# POWERSYSTEM.net
KiCad netlist of a schematic drawn in Altium Designer
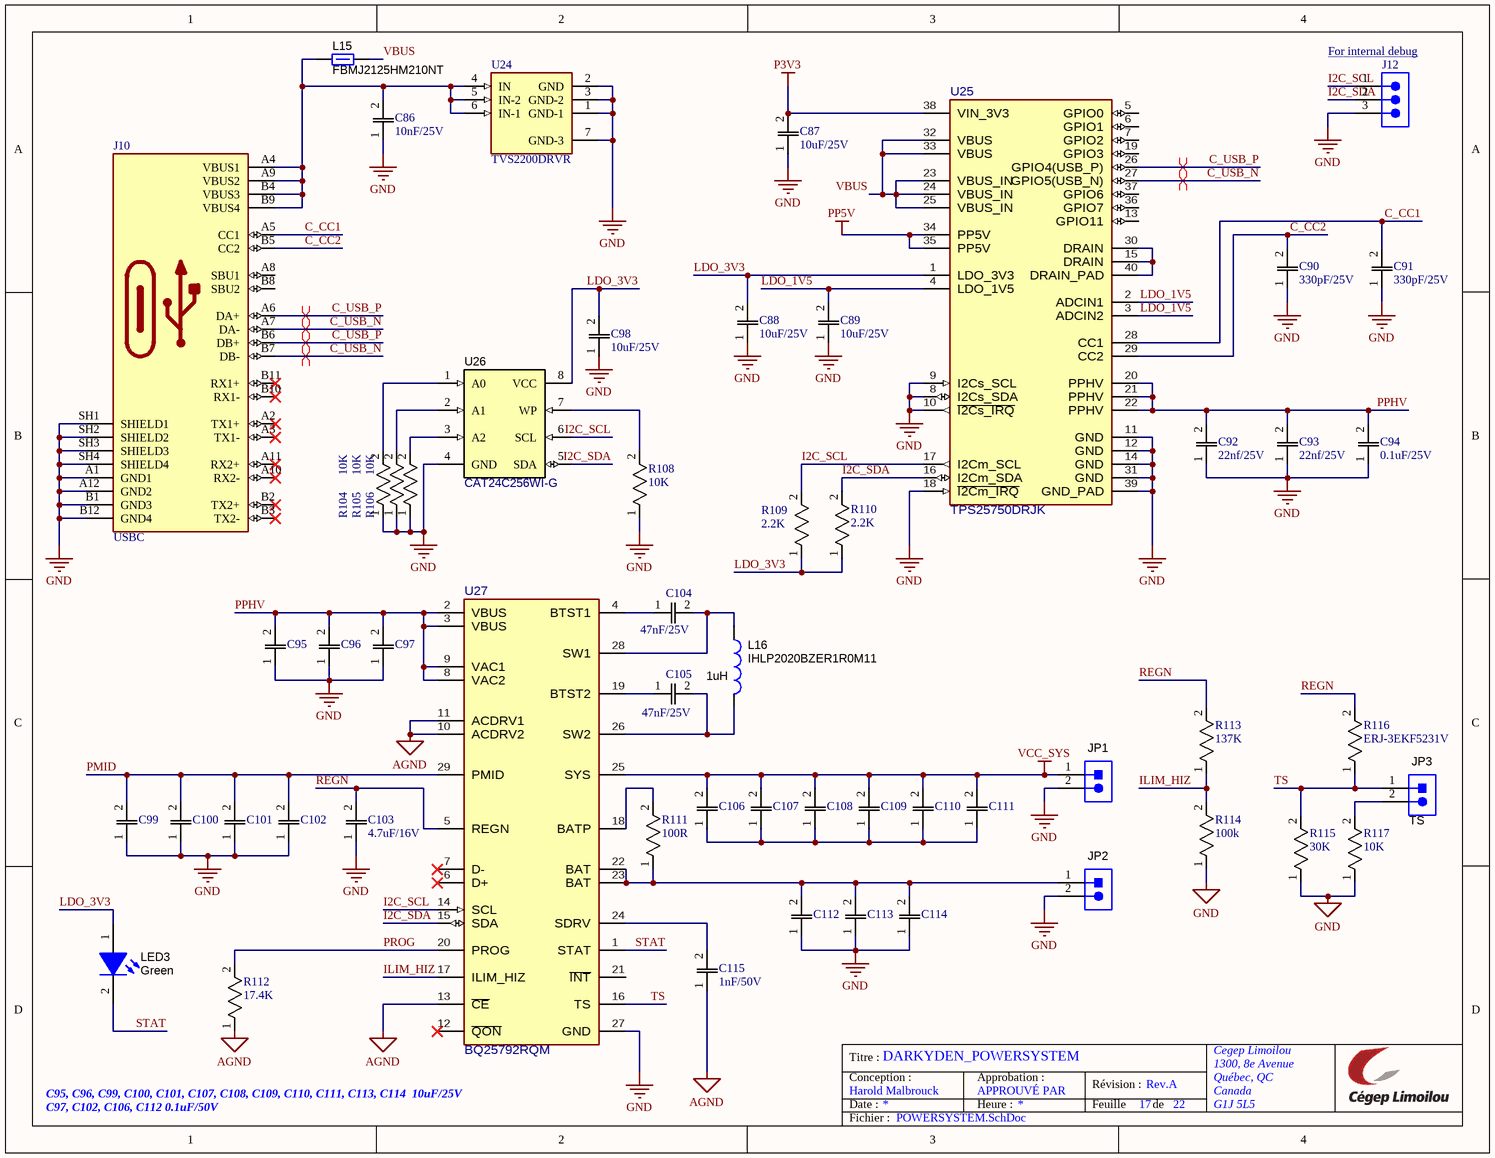
[diagram p0: POWERSYSTEM.SchDoc]

(export (version "E")
  (design (tool "Eeschema 10.0.6"))
  (components
    (comp (ref "C86")
      (value "10nF/25V")
      (footprint "SamacSys:C0805")
      (description "SMD Comm X7R")
      (fields (field (name "MANUFACTURER_PART_NUMBER") "C0805C103K3RACTU"))
      (libsource (lib "SamacSys") (part "C0805C103K3RACTU"))
    )
    (comp (ref "C87")
      (value "10uF/25V")
      (footprint "CAPC220145_88N_KEM")
      (description "10uF / 25 VDC, +85degC, X5R Dielec, +/-10% ¦ KEMET C0805C106K3PACTU 0805")
      (fields
        (field (name "MANUFACTURER") "KEMET")
        (field (name "MANUFACTURER PART NUMBER") "C0805C106K3PACTU")
      )
      (libsource (lib "C0805C106K3PACTU") (part "C0805C106K3PACTU"))
    )
    (comp (ref "C88")
      (value "10uF/25V")
      (footprint "CAPC220145_88N_KEM")
      (description "10uF / 25 VDC, +85degC, X5R Dielec, +/-10% ¦ KEMET C0805C106K3PACTU 0805")
      (fields
        (field (name "MANUFACTURER") "KEMET")
        (field (name "MANUFACTURER PART NUMBER") "C0805C106K3PACTU")
      )
      (libsource (lib "C0805C106K3PACTU") (part "C0805C106K3PACTU"))
    )
    (comp (ref "C89")
      (value "10uF/25V")
      (footprint "CAPC220145_88N_KEM")
      (description "10uF / 25 VDC, +85degC, X5R Dielec, +/-10% ¦ KEMET C0805C106K3PACTU 0805")
      (fields
        (field (name "MANUFACTURER") "KEMET")
        (field (name "MANUFACTURER PART NUMBER") "C0805C106K3PACTU")
      )
      (libsource (lib "C0805C106K3PACTU") (part "C0805C106K3PACTU"))
    )
    (comp (ref "C90")
      (value "330pF/25V")
      (footprint "SamacSys:C0805")
      (description "330pF/25V  C0G 0805 10%")
      (fields
        (field (name "MANUFACTURER_PART_NUMBER") "C0805C331K3GACTU")
        (field (name "MOUSER PART NUMBER") "80-C0805C331K3G")
      )
      (libsource (lib "SamacSys") (part "C0805C331K3GACTU"))
    )
    (comp (ref "C91")
      (value "330pF/25V")
      (footprint "SamacSys:C0805")
      (description "330pF/25V  C0G 0805 10%")
      (fields
        (field (name "MANUFACTURER_PART_NUMBER") "C0805C331K3GACTU")
        (field (name "MOUSER PART NUMBER") "80-C0805C331K3G")
      )
      (libsource (lib "SamacSys") (part "C0805C331K3GACTU"))
    )
    (comp (ref "C92")
      (value "22nf/25V")
      (footprint "SamacSys:C0805")
      (description "SMD Multilayer Ceramic Capacitor, 0.022 ï¿½F, 25 V, 0805 [2012 Metric], ï¿½ 5%, C0G / NP0")
      (fields
        (field (name "MANUFACTURER_PART_NUMBER") "C0805C223J3GACTU")
        (field (name "MANUFACTURER") "KEMET")
      )
      (libsource (lib "SamacSys") (part "C0805C223J3GACTU"))
    )
    (comp (ref "C93")
      (value "22nf/25V")
      (footprint "SamacSys:C0805")
      (description "SMD Multilayer Ceramic Capacitor, 0.022 ï¿½F, 25 V, 0805 [2012 Metric], ï¿½ 5%, C0G / NP0")
      (fields
        (field (name "MANUFACTURER_PART_NUMBER") "C0805C223J3GACTU")
        (field (name "MANUFACTURER") "KEMET")
      )
      (libsource (lib "SamacSys") (part "C0805C223J3GACTU"))
    )
    (comp (ref "C94")
      (value "0.1uF/25V")
      (footprint "CAPC220145_88N_KEM")
      (description "0.1uF 25V X7R 10% SMD 0805 125C Plastic T/R")
      (fields
        (field (name "MANUFACTURER") "KEMET")
        (field (name "MANUFACTURER PART NUMBER") "C0805C104K3RACTU")
      )
      (libsource (lib "C0805C104K3RACTU") (part "C0805C104K3RACTU"))
    )
    (comp (ref "C95")
      (value "10uF/25V")
      (footprint "CAPC220145_88N_KEM")
      (description "10uF / 25 VDC, +85degC, X5R Dielec, +/-10% ¦ KEMET C0805C106K3PACTU 0805")
      (fields
        (field (name "MANUFACTURER") "KEMET")
        (field (name "MANUFACTURER PART NUMBER") "C0805C106K3PACTU")
      )
      (libsource (lib "C0805C106K3PACTU") (part "C0805C106K3PACTU"))
    )
    (comp (ref "C96")
      (value "10uF/25V")
      (footprint "CAPC220145_88N_KEM")
      (description "10uF / 25 VDC, +85degC, X5R Dielec, +/-10% ¦ KEMET C0805C106K3PACTU 0805")
      (fields
        (field (name "MANUFACTURER") "KEMET")
        (field (name "MANUFACTURER PART NUMBER") "C0805C106K3PACTU")
      )
      (libsource (lib "C0805C106K3PACTU") (part "C0805C106K3PACTU"))
    )
    (comp (ref "C97")
      (value "0.1uF/50V")
      (footprint "SamacSys:C0805")
      (description "SMD Comm X7R")
      (fields (field (name "MANUFACTURER_PART_NUMBER") "C0805C104K5RACTU"))
      (libsource (lib "SamacSys") (part "C0805C104K5RACTU"))
    )
    (comp (ref "C98")
      (value "10uF/25V")
      (footprint "CAPC220145_88N_KEM")
      (description "10uF / 25 VDC, +85degC, X5R Dielec, +/-10% ¦ KEMET C0805C106K3PACTU 0805")
      (fields
        (field (name "MANUFACTURER") "KEMET")
        (field (name "MANUFACTURER PART NUMBER") "C0805C106K3PACTU")
      )
      (libsource (lib "C0805C106K3PACTU") (part "C0805C106K3PACTU"))
    )
    (comp (ref "C99")
      (value "10uF/25V")
      (footprint "CAPC220145_88N_KEM")
      (description "10uF / 25 VDC, +85degC, X5R Dielec, +/-10% ¦ KEMET C0805C106K3PACTU 0805")
      (fields
        (field (name "MANUFACTURER") "KEMET")
        (field (name "MANUFACTURER PART NUMBER") "C0805C106K3PACTU")
      )
      (libsource (lib "C0805C106K3PACTU") (part "C0805C106K3PACTU"))
    )
    (comp (ref "C100")
      (value "10uF/25V")
      (footprint "CAPC220145_88N_KEM")
      (description "10uF / 25 VDC, +85degC, X5R Dielec, +/-10% ¦ KEMET C0805C106K3PACTU 0805")
      (fields
        (field (name "MANUFACTURER") "KEMET")
        (field (name "MANUFACTURER PART NUMBER") "C0805C106K3PACTU")
      )
      (libsource (lib "C0805C106K3PACTU") (part "C0805C106K3PACTU"))
    )
    (comp (ref "C101")
      (value "10uF/25V")
      (footprint "CAPC220145_88N_KEM")
      (description "10uF / 25 VDC, +85degC, X5R Dielec, +/-10% ¦ KEMET C0805C106K3PACTU 0805")
      (fields
        (field (name "MANUFACTURER") "KEMET")
        (field (name "MANUFACTURER PART NUMBER") "C0805C106K3PACTU")
      )
      (libsource (lib "C0805C106K3PACTU") (part "C0805C106K3PACTU"))
    )
    (comp (ref "C102")
      (value "0.1uF/50V")
      (footprint "SamacSys:C0805")
      (description "SMD Comm X7R")
      (fields (field (name "MANUFACTURER_PART_NUMBER") "C0805C104K5RACTU"))
      (libsource (lib "SamacSys") (part "C0805C104K5RACTU"))
    )
    (comp (ref "C103")
      (value "4.7uF/16V")
      (footprint "SamacSys:C0805")
      (description "4.7 uF, 16 V, ± 10%, X7R, 0805 [2012 Metric]")
      (fields
        (field (name "MANUFACTURER_PART_NUMBER") "C0805C475K4RACTU")
        (field (name "MOUSER PART NUMBER") "80-C0805C475K4R")
      )
      (libsource (lib "SamacSys") (part "C0805C475K4RACTU"))
    )
    (comp (ref "C104")
      (value "47nF/25V")
      (footprint "SamacSys:C0805")
      (description "47nF /25 V, +125degC, C0G Dielectric, +/-5% ¦ KEMET C0805C473J3GACTU")
      (fields
        (field (name "MANUFACTURER_PART_NUMBER") "C0805C473J3GACTU")
        (field (name "MOUSER PART NUMBER") "80-C0805C473J3G")
      )
      (libsource (lib "SamacSys") (part "C0805C473J3GACTU"))
    )
    (comp (ref "C105")
      (value "47nF/25V")
      (footprint "SamacSys:C0805")
      (description "47nF /25 V, +125degC, C0G Dielectric, +/-5% ¦ KEMET C0805C473J3GACTU")
      (fields
        (field (name "MANUFACTURER_PART_NUMBER") "C0805C473J3GACTU")
        (field (name "MOUSER PART NUMBER") "80-C0805C473J3G")
      )
      (libsource (lib "SamacSys") (part "C0805C473J3GACTU"))
    )
    (comp (ref "C106")
      (value "0.1uF/50V")
      (footprint "SamacSys:C0805")
      (description "SMD Comm X7R")
      (fields (field (name "MANUFACTURER_PART_NUMBER") "C0805C104K5RACTU"))
      (libsource (lib "SamacSys") (part "C0805C104K5RACTU"))
    )
    (comp (ref "C107")
      (value "10uF/25V")
      (footprint "CAPC220145_88N_KEM")
      (description "10uF / 25 VDC, +85degC, X5R Dielec, +/-10% ¦ KEMET C0805C106K3PACTU 0805")
      (fields
        (field (name "MANUFACTURER") "KEMET")
        (field (name "MANUFACTURER PART NUMBER") "C0805C106K3PACTU")
      )
      (libsource (lib "C0805C106K3PACTU") (part "C0805C106K3PACTU"))
    )
    (comp (ref "C108")
      (value "10uF/25V")
      (footprint "CAPC220145_88N_KEM")
      (description "10uF / 25 VDC, +85degC, X5R Dielec, +/-10% ¦ KEMET C0805C106K3PACTU 0805")
      (fields
        (field (name "MANUFACTURER") "KEMET")
        (field (name "MANUFACTURER PART NUMBER") "C0805C106K3PACTU")
      )
      (libsource (lib "C0805C106K3PACTU") (part "C0805C106K3PACTU"))
    )
    (comp (ref "C109")
      (value "10uF/25V")
      (footprint "CAPC220145_88N_KEM")
      (description "10uF / 25 VDC, +85degC, X5R Dielec, +/-10% ¦ KEMET C0805C106K3PACTU 0805")
      (fields
        (field (name "MANUFACTURER") "KEMET")
        (field (name "MANUFACTURER PART NUMBER") "C0805C106K3PACTU")
      )
      (libsource (lib "C0805C106K3PACTU") (part "C0805C106K3PACTU"))
    )
    (comp (ref "C110")
      (value "10uF/25V")
      (footprint "CAPC220145_88N_KEM")
      (description "10uF / 25 VDC, +85degC, X5R Dielec, +/-10% ¦ KEMET C0805C106K3PACTU 0805")
      (fields
        (field (name "MANUFACTURER") "KEMET")
        (field (name "MANUFACTURER PART NUMBER") "C0805C106K3PACTU")
      )
      (libsource (lib "C0805C106K3PACTU") (part "C0805C106K3PACTU"))
    )
    (comp (ref "C111")
      (value "10uF/25V")
      (footprint "CAPC220145_88N_KEM")
      (description "10uF / 25 VDC, +85degC, X5R Dielec, +/-10% ¦ KEMET C0805C106K3PACTU 0805")
      (fields
        (field (name "MANUFACTURER") "KEMET")
        (field (name "MANUFACTURER PART NUMBER") "C0805C106K3PACTU")
      )
      (libsource (lib "C0805C106K3PACTU") (part "C0805C106K3PACTU"))
    )
    (comp (ref "C112")
      (value "0.1uF/50V")
      (footprint "SamacSys:C0805")
      (description "SMD Comm X7R")
      (fields (field (name "MANUFACTURER_PART_NUMBER") "C0805C104K5RACTU"))
      (libsource (lib "SamacSys") (part "C0805C104K5RACTU"))
    )
    (comp (ref "C113")
      (value "10uF/25V")
      (footprint "CAPC220145_88N_KEM")
      (description "10uF / 25 VDC, +85degC, X5R Dielec, +/-10% ¦ KEMET C0805C106K3PACTU 0805")
      (fields
        (field (name "MANUFACTURER") "KEMET")
        (field (name "MANUFACTURER PART NUMBER") "C0805C106K3PACTU")
      )
      (libsource (lib "C0805C106K3PACTU") (part "C0805C106K3PACTU"))
    )
    (comp (ref "C114")
      (value "10uF/25V")
      (footprint "CAPC220145_88N_KEM")
      (description "10uF / 25 VDC, +85degC, X5R Dielec, +/-10% ¦ KEMET C0805C106K3PACTU 0805")
      (fields
        (field (name "MANUFACTURER") "KEMET")
        (field (name "MANUFACTURER PART NUMBER") "C0805C106K3PACTU")
      )
      (libsource (lib "C0805C106K3PACTU") (part "C0805C106K3PACTU"))
    )
    (comp (ref "C115")
      (value "1nF/50V")
      (footprint "SamacSys:CAPC2012X88N")
      (description "Multilayer Ceramic Capacitor 1000 Pf 50 V ½ 10% X7R 0805 [2012 Metric]")
      (fields
        (field (name "MANUFACTURER_PART_NUMBER") "C0805C102K5RAC-TU")
        (field (name "MANUFACTURER") "KEMET")
      )
      (libsource (lib "SamacSys") (part "C0805C102K5RACTU"))
    )
    (comp (ref "J10")
      (value "USBC")
      (footprint "MOLEX_2012670005")
      (fields (field (name "MF") "Molex") (field (name "MP") "2012670005"))
      (libsource (lib "USBC") (part "USBC"))
    )
    (comp (ref "J12")
      (value "61300311121")
      (footprint "61300311121")
      (description "WR-PHD Pin Header, THT, Vertical, pitch 2.54mm, 1 Row, 3P")
      (fields (field (name "MANUFACTURER") "Wurth Elektronik"))
      (libsource (lib "Header") (part "61300311121"))
    )
    (comp (ref "JP1")
      (value "Header_2x1")
      (footprint "CONN_PEC02SAAN")
      (description "Header, 100mil, 2x1, Tin, TH")
      (fields
        (field (name "PARTNUMBER") "PEC02SAAN")
        (field (name "MANUFACTURER") "Sullins Connector Solutions")
        (field (name "PUBLISHER") "Texas Instruments")
      )
      (libsource (lib "texas_instrument_power") (part "Header_2x1"))
    )
    (comp (ref "JP2")
      (value "Header_2x1")
      (footprint "CONN_PEC02SAAN")
      (description "Header, 100mil, 2x1, Tin, TH")
      (fields
        (field (name "PARTNUMBER") "PEC02SAAN")
        (field (name "MANUFACTURER") "Sullins Connector Solutions")
        (field (name "PUBLISHER") "Texas Instruments")
      )
      (libsource (lib "texas_instrument_power") (part "Header_2x1"))
    )
    (comp (ref "JP3")
      (value "TS")
      (footprint "CONN_PEC02SAAN")
      (description "Header, 100mil, 2x1, Tin, TH")
      (fields
        (field (name "PARTNUMBER") "PEC02SAAN")
        (field (name "MANUFACTURER") "Sullins Connector Solutions")
        (field (name "PUBLISHER") "Texas Instruments")
      )
      (libsource (lib "texas_instrument_power") (part "Header_2x1"))
    )
    (comp (ref "L15")
      (value "FBMJ2125HM210NT")
      (footprint "0805_HV")
      (description "Ferrite Bead, 21 ohm @ 100 MHz, 6 A, 0805")
      (fields (field (name "MANUFACTURER") "Taiyo Yuden") (field (name "PUBLISHER") "Texas Instruments"))
      (libsource (lib "Altium Vault - TI") (part "Ferrite_Bead"))
    )
    (comp (ref "L16")
      (value "IHLP2020BZER1R0M11")
      (footprint "IHLP-2020BZ")
      (description "Inductor, Shielded Drum Core, Powdered Iron, 1 uH, 7 A, 0.0181 ohm, SMD")
      (fields
        (field (name "MANUFACTURER") "Vishay-Dale")
        (field (name "VALUEDISPLAYED") "1uH")
        (field (name "PUBLISHER") "Texas Instruments")
      )
      (libsource (lib "texas_instrument_power") (part "IHLP2020BZER1R0M11"))
    )
    (comp (ref "LED3")
      (value "Green")
      (footprint "LED_LTST-C190")
      (description "LED, Green, SMD")
      (fields (field (name "MANUFACTURER") "Lite-On") (field (name "PARTNUMBER") "LTST-C190GKT"))
      (libsource (lib "texas_instrument_power") (part "LED_Gr_SMD"))
    )
    (comp (ref "R104")
      (value "10K")
      (footprint "SamacSys:ERJ3EKF1000V")
      (description "10K Ohm 5% Res Thick Film 0603  0.1W(1/10W) ±200ppm/C Pad SMD Automotive T/R")
      (fields
        (field (name "MANUFACTURER_PART_NUMBER") "ERJ-3GEYJ103V")
        (field (name "MOUSER PART NUMBER") "667-ERJ-3GEYJ103V")
      )
      (libsource (lib "SamacSys") (part "ERJ-3GEYJ103V"))
    )
    (comp (ref "R105")
      (value "10K")
      (footprint "SamacSys:ERJ3EKF1000V")
      (description "10K Ohm 5% Res Thick Film 0603  0.1W(1/10W) ±200ppm/C Pad SMD Automotive T/R")
      (fields
        (field (name "MANUFACTURER_PART_NUMBER") "ERJ-3GEYJ103V")
        (field (name "MOUSER PART NUMBER") "667-ERJ-3GEYJ103V")
      )
      (libsource (lib "SamacSys") (part "ERJ-3GEYJ103V"))
    )
    (comp (ref "R106")
      (value "10K")
      (footprint "SamacSys:ERJ3EKF1000V")
      (description "10K Ohm 5% Res Thick Film 0603  0.1W(1/10W) ±200ppm/C Pad SMD Automotive T/R")
      (fields
        (field (name "MANUFACTURER_PART_NUMBER") "ERJ-3GEYJ103V")
        (field (name "MOUSER PART NUMBER") "667-ERJ-3GEYJ103V")
      )
      (libsource (lib "SamacSys") (part "ERJ-3GEYJ103V"))
    )
    (comp (ref "R108")
      (value "10K")
      (footprint "SamacSys:ERJ3EKF1000V")
      (description "10K Ohm 5% Res Thick Film 0603  0.1W(1/10W) ±200ppm/C Pad SMD Automotive T/R")
      (fields
        (field (name "MANUFACTURER_PART_NUMBER") "ERJ-3GEYJ103V")
        (field (name "MOUSER PART NUMBER") "667-ERJ-3GEYJ103V")
      )
      (libsource (lib "SamacSys") (part "ERJ-3GEYJ103V"))
    )
    (comp (ref "R109")
      (value "2.2K")
      (footprint "SamacSys:ERJ3EKF1000V")
      (description "SMD Chip Resistor, 2.2 kOhm, ï¿½ 5%, 100 mW, 0603 [1608 Metric], Thick Film, General Purpose")
      (fields
        (field (name "MANUFACTURER_PART_NUMBER") "ERJ-3GEYJ222V")
        (field (name "MOUSER PART NUMBER") "667-ERJ-3GEYJ222V")
      )
      (libsource (lib "SamacSys") (part "ERJ-3GEYJ222V"))
    )
    (comp (ref "R110")
      (value "2.2K")
      (footprint "SamacSys:ERJ3EKF1000V")
      (description "SMD Chip Resistor, 2.2 kOhm, ï¿½ 5%, 100 mW, 0603 [1608 Metric], Thick Film, General Purpose")
      (fields
        (field (name "MANUFACTURER_PART_NUMBER") "ERJ-3GEYJ222V")
        (field (name "MOUSER PART NUMBER") "667-ERJ-3GEYJ222V")
      )
      (libsource (lib "SamacSys") (part "ERJ-3GEYJ222V"))
    )
    (comp (ref "R111")
      (value "100R")
      (footprint "SamacSys:RESC1608X55N")
      (description "100 Ohm 1% 1/10W 0603 ±100ppm/°C Molded SMD Punched Carrier T/R")
      (fields
        (field (name "MANUFACTURER_PART_NUMBER") "ERJ-3EKF1000V")
        (field (name "MOUSER PART NUMBER") "667-ERJ-3EKF1000V")
      )
      (libsource (lib "SamacSys") (part "ERJ-3EKF1000V"))
    )
    (comp (ref "R112")
      (value "17.4K")
      (footprint "SamacSys:RESC1608X55N")
      (description "Res Thick Film 0603 17.4K Ohm 1% 1/10W +/-100ppm/ßC Molded SMD Punched Carrier T/R")
      (fields
        (field (name "MANUFACTURER_PART_NUMBER") "ERJ-3EKF1742V")
        (field (name "MOUSER PART NUMBER") "667-ERJ-3EKF1742V")
      )
      (libsource (lib "SamacSys") (part "ERJ-3EKF1742V"))
    )
    (comp (ref "R113")
      (value "137K")
      (footprint "SamacSys:RESC1608X55N")
      (description "137K Ohm 1% 1/10W Res Thick Film 0603 ±100ppm/°C SMD Punched Carrier T/R")
      (fields
        (field (name "MANUFACTURER_PART_NUMBER") "ERJ-3EKF1373V")
        (field (name "MOUSER PART NUMBER") "667-ERJ-3EKF1373V")
      )
      (libsource (lib "SamacSys") (part "ERJ-3EKF1373V"))
    )
    (comp (ref "R114")
      (value "100k")
      (footprint "SamacSys:ERJ3EKF1000V")
      (description "100K Ohm 5%  Res Thick Film 0603 1/10W +/-200ppm/ßC Molded SMD Punched Carrier T/R")
      (fields
        (field (name "MANUFACTURER_PART_NUMBER") "ERJ-3GEYJ104V")
        (field (name "MOUSER PART NUMBER") "667-ERJ-3GEYJ104V")
      )
      (libsource (lib "SamacSys") (part "ERJ-3GEYJ104V"))
    )
    (comp (ref "R115")
      (value "30K")
      (footprint "SamacSys:ERJ3EKF1000V")
      (description "30K Ohm 5% 0.1W(1/10W) +/-200ppm/ßC Res Thick Film 0603  SMD Automotive T/R")
      (fields
        (field (name "MANUFACTURER_PART_NUMBER") "ERJ-3GEYJ303V")
        (field (name "MOUSER PART NUMBER") "667-ERJ-3GEYJ303V")
      )
      (libsource (lib "SamacSys") (part "ERJ-3GEYJ303V"))
    )
    (comp (ref "R116")
      (value "ERJ-3EKF5231V")
      (footprint "SamacSys:RESC1608X55N")
      (description "5.23K Ohm 1% 1/10W Res Thick Film 0603+/-100ppm/ßC Molded SMD Punched Carrier T/R")
      (fields
        (field (name "MOUSER PART NUMBER") "667-ERJ-3EKF5231V")
        (field (name "MANUFACTURER") "Panasonic")
      )
      (libsource (lib "SamacSys") (part "ERJ-3EKF5231V"))
    )
    (comp (ref "R117")
      (value "10K")
      (footprint "SamacSys:ERJ3EKF1000V")
      (description "10K Ohm 5% Res Thick Film 0603  0.1W(1/10W) ±200ppm/C Pad SMD Automotive T/R")
      (fields
        (field (name "MANUFACTURER_PART_NUMBER") "ERJ-3GEYJ103V")
        (field (name "MOUSER PART NUMBER") "667-ERJ-3GEYJ103V")
      )
      (libsource (lib "SamacSys") (part "ERJ-3GEYJ103V"))
    )
    (comp (ref "U24")
      (value "TVS2200DRVR")
      (footprint "SON65P200X200X80-7N")
      (description "ESD Suppressors / TVS Diodes 22V flat-clamp surge protection device 6-WSON -40 to 125")
      (fields (field (name "MF") "Texas Instruments"))
      (libsource (lib "TVS2200") (part "TVS2200DRVR"))
    )
    (comp (ref "U25")
      (value "TPS25750DRJK")
      (footprint "RJK0038B-C01-MFG")
      (description "USB Type-C and USB PD Controller with Integrated Power Switches Optimized for Power Applications")
      (fields (field (name "MANUFACTURER") "Texas Instruments"))
      (libsource (lib "PD_BQ_Ref_Design") (part "TPS25750DRJK"))
    )
    (comp (ref "U26")
      (value "CAT24C256WI-G")
      (footprint "SOIC-8")
      (description "256 kb I2C CMOS Serial EEPROM, SOIC-8")
      (fields (field (name "MANUFACTURER") "ON Semiconductor") (field (name "PUBLISHER") "Texas Instruments"))
      (libsource (lib "PD_BQ_Ref_Design") (part "CAT24C256WI-G"))
    )
    (comp (ref "U27")
      (value "BQ25792RQM")
      (footprint "RQM0029A-MFG")
      (description "BQ2579x HotRod")
      (fields (field (name "MANUFACTURER") "Texas Instruments"))
      (libsource (lib "PD_BQ_Ref_Design") (part "BQ2579x"))
    )
  )
  (nets
    (net (code "1") (name "/C_CC1") (class "Default")
      (node (ref "C91") (pin "2") (pinfunction "2_2") (pintype "passive"))
      (node (ref "J10") (pin "A5") (pinfunction "CC1_A5") (pintype "bidirectional"))
      (node (ref "U25") (pin "28") (pinfunction "CC1_28") (pintype "passive"))
    )
    (net (code "2") (name "/C_CC2") (class "Default")
      (node (ref "C90") (pin "2") (pinfunction "2_2") (pintype "passive"))
      (node (ref "J10") (pin "B5") (pinfunction "CC2_B5") (pintype "bidirectional"))
      (node (ref "U25") (pin "29") (pinfunction "CC2_29") (pintype "passive"))
    )
    (net (code "3") (name "/C_USB_N") (class "Default")
      (node (ref "J10") (pin "A7") (pinfunction "DA-_A7") (pintype "bidirectional"))
      (node (ref "J10") (pin "B7") (pinfunction "DB-_B7") (pintype "bidirectional"))
      (node (ref "U25") (pin "27") (pinfunction "GPIO5(USB_N)_27") (pintype "bidirectional"))
    )
    (net (code "4") (name "/C_USB_P") (class "Default")
      (node (ref "J10") (pin "A6") (pinfunction "DA+_A6") (pintype "bidirectional"))
      (node (ref "J10") (pin "B6") (pinfunction "DB+_B6") (pintype "bidirectional"))
      (node (ref "U25") (pin "26") (pinfunction "GPIO4(USB_P)_26") (pintype "bidirectional"))
    )
    (net (code "5") (name "/I2C_SCL") (class "Default")
      (node (ref "J12") (pin "1") (pinfunction "1_1") (pintype "passive"))
      (node (ref "R109") (pin "2") (pinfunction "2_2") (pintype "passive"))
      (node (ref "U25") (pin "17") (pinfunction "I2Cm_SCL_17") (pintype "output"))
      (node (ref "U26") (pin "6") (pinfunction "SCL_6") (pintype "input"))
      (node (ref "U27") (pin "14") (pinfunction "SCL_14") (pintype "input"))
    )
    (net (code "6") (name "/I2C_SDA") (class "Default")
      (node (ref "J12") (pin "2") (pinfunction "2_2") (pintype "passive"))
      (node (ref "R110") (pin "2") (pinfunction "2_2") (pintype "passive"))
      (node (ref "U25") (pin "16") (pinfunction "I2Cm_SDA_16") (pintype "bidirectional"))
      (node (ref "U26") (pin "5") (pinfunction "SDA_5") (pintype "bidirectional"))
      (node (ref "U27") (pin "15") (pinfunction "SDA_15") (pintype "bidirectional"))
    )
    (net (code "7") (name "/ILIM_HIZ") (class "Default")
      (node (ref "R113") (pin "1") (pinfunction "1_1") (pintype "passive"))
      (node (ref "R114") (pin "2") (pinfunction "2_2") (pintype "passive"))
      (node (ref "U27") (pin "17") (pinfunction "ILIM_HIZ_17") (pintype "passive"))
    )
    (net (code "8") (name "/LDO_1V5") (class "Default")
      (node (ref "C89") (pin "2") (pinfunction "2_2") (pintype "passive"))
      (node (ref "U25") (pin "2") (pinfunction "ADCIN1_2") (pintype "passive"))
      (node (ref "U25") (pin "3") (pinfunction "ADCIN2_3") (pintype "passive"))
      (node (ref "U25") (pin "4") (pinfunction "LDO_1V5_4") (pintype "passive"))
    )
    (net (code "9") (name "/LDO_3V3") (class "Default")
      (node (ref "C88") (pin "2") (pinfunction "2_2") (pintype "passive"))
      (node (ref "C98") (pin "2") (pinfunction "2_2") (pintype "passive"))
      (node (ref "LED3") (pin "1") (pinfunction "A_1") (pintype "passive"))
      (node (ref "R109") (pin "1") (pinfunction "1_1") (pintype "passive"))
      (node (ref "R110") (pin "1") (pinfunction "1_1") (pintype "passive"))
      (node (ref "U25") (pin "1") (pinfunction "LDO_3V3_1") (pintype "passive"))
      (node (ref "U26") (pin "8") (pinfunction "VCC_8") (pintype "power_in"))
    )
    (net (code "10") (name "/PMID") (class "Default")
      (node (ref "C100") (pin "2") (pinfunction "2_2") (pintype "passive"))
      (node (ref "C101") (pin "2") (pinfunction "2_2") (pintype "passive"))
      (node (ref "C102") (pin "2") (pinfunction "2_2") (pintype "passive"))
      (node (ref "C99") (pin "2") (pinfunction "2_2") (pintype "passive"))
      (node (ref "U27") (pin "29") (pinfunction "PMID_29") (pintype "passive"))
    )
    (net (code "11") (name "/PPHV") (class "Default")
      (node (ref "C92") (pin "2") (pinfunction "2_2") (pintype "passive"))
      (node (ref "C93") (pin "2") (pinfunction "2_2") (pintype "passive"))
      (node (ref "C94") (pin "2") (pinfunction "2_2") (pintype "passive"))
      (node (ref "C95") (pin "2") (pinfunction "2_2") (pintype "passive"))
      (node (ref "C96") (pin "2") (pinfunction "2_2") (pintype "passive"))
      (node (ref "C97") (pin "2") (pinfunction "2_2") (pintype "passive"))
      (node (ref "U25") (pin "20") (pinfunction "PPHV_20") (pintype "passive"))
      (node (ref "U25") (pin "21") (pinfunction "PPHV_21") (pintype "passive"))
      (node (ref "U25") (pin "22") (pinfunction "PPHV_22") (pintype "passive"))
      (node (ref "U27") (pin "2") (pinfunction "VBUS_2") (pintype "power_in"))
      (node (ref "U27") (pin "3") (pinfunction "VBUS_3") (pintype "power_in"))
      (node (ref "U27") (pin "8") (pinfunction "VAC2_8") (pintype "power_in"))
      (node (ref "U27") (pin "9") (pinfunction "VAC1_9") (pintype "power_in"))
    )
    (net (code "12") (name "/PROG") (class "Default")
      (node (ref "R112") (pin "2") (pinfunction "2_2") (pintype "passive"))
      (node (ref "U27") (pin "20") (pinfunction "PROG_20") (pintype "passive"))
    )
    (net (code "13") (name "/REGN") (class "Default")
      (node (ref "C103") (pin "2") (pinfunction "2_2") (pintype "passive"))
      (node (ref "R113") (pin "2") (pinfunction "2_2") (pintype "passive"))
      (node (ref "R116") (pin "2") (pinfunction "2_2") (pintype "passive"))
      (node (ref "U27") (pin "5") (pinfunction "REGN_5") (pintype "passive"))
    )
    (net (code "14") (name "/STAT") (class "Default")
      (node (ref "LED3") (pin "2") (pinfunction "K_2") (pintype "passive"))
      (node (ref "U27") (pin "1") (pinfunction "STAT_1") (pintype "passive"))
    )
    (net (code "15") (name "/TS") (class "Default")
      (node (ref "JP3") (pin "1") (pinfunction "1_1") (pintype "passive"))
      (node (ref "R115") (pin "2") (pinfunction "2_2") (pintype "passive"))
      (node (ref "R116") (pin "1") (pinfunction "1_1") (pintype "passive"))
      (node (ref "U27") (pin "16") (pinfunction "TS_16") (pintype "passive"))
    )
    (net (code "16") (name "/VBUS") (class "Default")
      (node (ref "L15") (pin "2") (pinfunction "2_2") (pintype "passive"))
      (node (ref "U25") (pin "23") (pinfunction "VBUS_IN_23") (pintype "power_in"))
      (node (ref "U25") (pin "24") (pinfunction "VBUS_IN_24") (pintype "power_in"))
      (node (ref "U25") (pin "25") (pinfunction "VBUS_IN_25") (pintype "power_in"))
      (node (ref "U25") (pin "32") (pinfunction "VBUS_32") (pintype "power_in"))
      (node (ref "U25") (pin "33") (pinfunction "VBUS_33") (pintype "power_in"))
    )
    (net (code "17") (name "AGND") (class "Default")
      (node (ref "C115") (pin "1") (pinfunction "1_1") (pintype "passive"))
      (node (ref "R112") (pin "1") (pinfunction "1_1") (pintype "passive"))
      (node (ref "U27") (pin "10") (pinfunction "ACDRV2_10") (pintype "power_in"))
      (node (ref "U27") (pin "11") (pinfunction "ACDRV1_11") (pintype "power_in"))
      (node (ref "U27") (pin "13") (pinfunction "~{CE}_13") (pintype "passive"))
    )
    (net (code "18") (name "GND") (class "Default")
      (node (ref "C100") (pin "1") (pinfunction "1_1") (pintype "passive"))
      (node (ref "C101") (pin "1") (pinfunction "1_1") (pintype "passive"))
      (node (ref "C102") (pin "1") (pinfunction "1_1") (pintype "passive"))
      (node (ref "C103") (pin "1") (pinfunction "1_1") (pintype "passive"))
      (node (ref "C112") (pin "1") (pinfunction "1_1") (pintype "passive"))
      (node (ref "C113") (pin "1") (pinfunction "1_1") (pintype "passive"))
      (node (ref "C114") (pin "1") (pinfunction "1_1") (pintype "passive"))
      (node (ref "C86") (pin "1") (pinfunction "1_1") (pintype "passive"))
      (node (ref "C87") (pin "1") (pinfunction "1_1") (pintype "passive"))
      (node (ref "C88") (pin "1") (pinfunction "1_1") (pintype "passive"))
      (node (ref "C89") (pin "1") (pinfunction "1_1") (pintype "passive"))
      (node (ref "C90") (pin "1") (pinfunction "1_1") (pintype "passive"))
      (node (ref "C91") (pin "1") (pinfunction "1_1") (pintype "passive"))
      (node (ref "C92") (pin "1") (pinfunction "1_1") (pintype "passive"))
      (node (ref "C93") (pin "1") (pinfunction "1_1") (pintype "passive"))
      (node (ref "C94") (pin "1") (pinfunction "1_1") (pintype "passive"))
      (node (ref "C95") (pin "1") (pinfunction "1_1") (pintype "passive"))
      (node (ref "C96") (pin "1") (pinfunction "1_1") (pintype "passive"))
      (node (ref "C97") (pin "1") (pinfunction "1_1") (pintype "passive"))
      (node (ref "C98") (pin "1") (pinfunction "1_1") (pintype "passive"))
      (node (ref "C99") (pin "1") (pinfunction "1_1") (pintype "passive"))
      (node (ref "J10") (pin "A1") (pinfunction "GND1_A1") (pintype "passive"))
      (node (ref "J10") (pin "A12") (pinfunction "GND2_A12") (pintype "passive"))
      (node (ref "J10") (pin "B1") (pinfunction "GND3_B1") (pintype "passive"))
      (node (ref "J10") (pin "B12") (pinfunction "GND4_B12") (pintype "passive"))
      (node (ref "J10") (pin "SH1") (pinfunction "SHIELD1_SH1") (pintype "passive"))
      (node (ref "J10") (pin "SH2") (pinfunction "SHIELD2_SH2") (pintype "passive"))
      (node (ref "J10") (pin "SH3") (pinfunction "SHIELD3_SH3") (pintype "passive"))
      (node (ref "J10") (pin "SH4") (pinfunction "SHIELD4_SH4") (pintype "passive"))
      (node (ref "J12") (pin "3") (pinfunction "3_3") (pintype "passive"))
      (node (ref "JP1") (pin "2") (pinfunction "2_2") (pintype "passive"))
      (node (ref "JP2") (pin "2") (pinfunction "2_2") (pintype "passive"))
      (node (ref "R104") (pin "1") (pinfunction "1_1") (pintype "passive"))
      (node (ref "R105") (pin "1") (pinfunction "1_1") (pintype "passive"))
      (node (ref "R106") (pin "1") (pinfunction "1_1") (pintype "passive"))
      (node (ref "R108") (pin "1") (pinfunction "1_1") (pintype "passive"))
      (node (ref "R114") (pin "1") (pinfunction "1_1") (pintype "passive"))
      (node (ref "R115") (pin "1") (pinfunction "1_1") (pintype "passive"))
      (node (ref "R117") (pin "1") (pinfunction "1_1") (pintype "passive"))
      (node (ref "U24") (pin "1") (pinfunction "GND-1_1") (pintype "passive"))
      (node (ref "U24") (pin "2") (pinfunction "GND_2") (pintype "passive"))
      (node (ref "U24") (pin "3") (pinfunction "GND-2_3") (pintype "passive"))
      (node (ref "U24") (pin "7") (pinfunction "GND-3_7") (pintype "passive"))
      (node (ref "U25") (pin "10") (pinfunction "~{I2Cs_IRQ}_10") (pintype "output"))
      (node (ref "U25") (pin "11") (pinfunction "GND_11") (pintype "passive"))
      (node (ref "U25") (pin "12") (pinfunction "GND_12") (pintype "passive"))
      (node (ref "U25") (pin "14") (pinfunction "GND_14") (pintype "passive"))
      (node (ref "U25") (pin "18") (pinfunction "~{I2Cm_IRQ}_18") (pintype "input"))
      (node (ref "U25") (pin "31") (pinfunction "GND_31") (pintype "passive"))
      (node (ref "U25") (pin "39") (pinfunction "GND_PAD_39") (pintype "passive"))
      (node (ref "U25") (pin "8") (pinfunction "I2Cs_SDA_8") (pintype "bidirectional"))
      (node (ref "U25") (pin "9") (pinfunction "I2Cs_SCL_9") (pintype "input"))
      (node (ref "U26") (pin "4") (pinfunction "GND_4") (pintype "passive"))
      (node (ref "U27") (pin "27") (pinfunction "GND_27") (pintype "passive"))
    )
    (net (code "19") (name "Net-(C106-Pad1)") (class "Default")
      (node (ref "C106") (pin "1") (pinfunction "1_1") (pintype "passive"))
      (node (ref "C107") (pin "1") (pinfunction "1_1") (pintype "passive"))
      (node (ref "C108") (pin "1") (pinfunction "1_1") (pintype "passive"))
      (node (ref "C109") (pin "1") (pinfunction "1_1") (pintype "passive"))
      (node (ref "C110") (pin "1") (pinfunction "1_1") (pintype "passive"))
      (node (ref "C111") (pin "1") (pinfunction "1_1") (pintype "passive"))
    )
    (net (code "20") (name "Net-(C112-Pad2)") (class "Default")
      (node (ref "C112") (pin "2") (pinfunction "2_2") (pintype "passive"))
      (node (ref "C113") (pin "2") (pinfunction "2_2") (pintype "passive"))
      (node (ref "C114") (pin "2") (pinfunction "2_2") (pintype "passive"))
      (node (ref "JP2") (pin "1") (pinfunction "1_1") (pintype "passive"))
      (node (ref "R111") (pin "1") (pinfunction "1_1") (pintype "passive"))
      (node (ref "U27") (pin "22") (pinfunction "BAT_22") (pintype "passive"))
      (node (ref "U27") (pin "23") (pinfunction "BAT_23") (pintype "passive"))
    )
    (net (code "21") (name "Net-(J10-VBUS1)") (class "Default")
      (node (ref "C86") (pin "2") (pinfunction "2_2") (pintype "passive"))
      (node (ref "J10") (pin "A4") (pinfunction "VBUS1_A4") (pintype "power_in"))
      (node (ref "J10") (pin "A9") (pinfunction "VBUS2_A9") (pintype "power_in"))
      (node (ref "J10") (pin "B4") (pinfunction "VBUS3_B4") (pintype "power_in"))
      (node (ref "J10") (pin "B9") (pinfunction "VBUS4_B9") (pintype "power_in"))
      (node (ref "L15") (pin "1") (pinfunction "1_1") (pintype "passive"))
      (node (ref "U24") (pin "4") (pinfunction "IN_4") (pintype "input"))
      (node (ref "U24") (pin "5") (pinfunction "IN-2_5") (pintype "input"))
      (node (ref "U24") (pin "6") (pinfunction "IN-1_6") (pintype "input"))
    )
    (net (code "22") (name "Net-(JP3-Pad2)") (class "Default")
      (node (ref "JP3") (pin "2") (pinfunction "2_2") (pintype "passive"))
      (node (ref "R117") (pin "2") (pinfunction "2_2") (pintype "passive"))
    )
    (net (code "23") (name "Net-(U25-DRAIN_PAD)") (class "Default")
      (node (ref "U25") (pin "15") (pinfunction "DRAIN_15") (pintype "passive"))
      (node (ref "U25") (pin "30") (pinfunction "DRAIN_30") (pintype "passive"))
      (node (ref "U25") (pin "40") (pinfunction "DRAIN_PAD_40") (pintype "passive"))
    )
    (net (code "24") (name "Net-(U26-A0)") (class "Default")
      (node (ref "R104") (pin "2") (pinfunction "2_2") (pintype "passive"))
      (node (ref "U26") (pin "1") (pinfunction "A0_1") (pintype "input"))
    )
    (net (code "25") (name "Net-(U26-A1)") (class "Default")
      (node (ref "R105") (pin "2") (pinfunction "2_2") (pintype "passive"))
      (node (ref "U26") (pin "2") (pinfunction "A1_2") (pintype "input"))
    )
    (net (code "26") (name "Net-(U26-A2)") (class "Default")
      (node (ref "R106") (pin "2") (pinfunction "2_2") (pintype "passive"))
      (node (ref "U26") (pin "3") (pinfunction "A2_3") (pintype "input"))
    )
    (net (code "27") (name "Net-(U26-WP)") (class "Default")
      (node (ref "R108") (pin "2") (pinfunction "2_2") (pintype "passive"))
      (node (ref "U26") (pin "7") (pinfunction "WP_7") (pintype "input"))
    )
    (net (code "28") (name "Net-(U27-BATP)") (class "Default")
      (node (ref "R111") (pin "2") (pinfunction "2_2") (pintype "passive"))
      (node (ref "U27") (pin "18") (pinfunction "BATP_18") (pintype "passive"))
    )
    (net (code "29") (name "Net-(U27-BTST1)") (class "Default")
      (node (ref "C104") (pin "1") (pinfunction "1_1") (pintype "passive"))
      (node (ref "U27") (pin "4") (pinfunction "BTST1_4") (pintype "passive"))
    )
    (net (code "30") (name "Net-(U27-BTST2)") (class "Default")
      (node (ref "C105") (pin "1") (pinfunction "1_1") (pintype "passive"))
      (node (ref "U27") (pin "19") (pinfunction "BTST2_19") (pintype "passive"))
    )
    (net (code "31") (name "Net-(U27-SDRV)") (class "Default")
      (node (ref "C115") (pin "2") (pinfunction "2_2") (pintype "passive"))
      (node (ref "U27") (pin "24") (pinfunction "SDRV_24") (pintype "passive"))
    )
    (net (code "32") (name "Net-(U27-SW1)") (class "Default")
      (node (ref "C104") (pin "2") (pinfunction "2_2") (pintype "passive"))
      (node (ref "L16") (pin "1") (pinfunction "1_1") (pintype "passive"))
      (node (ref "U27") (pin "28") (pinfunction "SW1_28") (pintype "passive"))
    )
    (net (code "33") (name "Net-(U27-SW2)") (class "Default")
      (node (ref "C105") (pin "2") (pinfunction "2_2") (pintype "passive"))
      (node (ref "L16") (pin "2") (pinfunction "2_2") (pintype "passive"))
      (node (ref "U27") (pin "26") (pinfunction "SW2_26") (pintype "passive"))
    )
    (net (code "34") (name "P3V3") (class "Default")
      (node (ref "C87") (pin "2") (pinfunction "2_2") (pintype "passive"))
      (node (ref "U25") (pin "38") (pinfunction "VIN_3V3_38") (pintype "power_in"))
    )
    (net (code "35") (name "PP5V") (class "Default")
      (node (ref "U25") (pin "34") (pinfunction "PP5V_34") (pintype "power_in"))
      (node (ref "U25") (pin "35") (pinfunction "PP5V_35") (pintype "power_in"))
    )
    (net (code "36") (name "VCC_SYS") (class "Default")
      (node (ref "C106") (pin "2") (pinfunction "2_2") (pintype "passive"))
      (node (ref "C107") (pin "2") (pinfunction "2_2") (pintype "passive"))
      (node (ref "C108") (pin "2") (pinfunction "2_2") (pintype "passive"))
      (node (ref "C109") (pin "2") (pinfunction "2_2") (pintype "passive"))
      (node (ref "C110") (pin "2") (pinfunction "2_2") (pintype "passive"))
      (node (ref "C111") (pin "2") (pinfunction "2_2") (pintype "passive"))
      (node (ref "JP1") (pin "1") (pinfunction "1_1") (pintype "passive"))
      (node (ref "U27") (pin "25") (pinfunction "SYS_25") (pintype "passive"))
    )
    (net (code "37") (name "unconnected-(J10-RX1+-PadB11)") (class "Default")
      (node (ref "J10") (pin "B11") (pinfunction "RX1+_B11") (pintype "bidirectional+no_connect"))
    )
    (net (code "38") (name "unconnected-(J10-RX1--PadB10)") (class "Default")
      (node (ref "J10") (pin "B10") (pinfunction "RX1-_B10") (pintype "bidirectional+no_connect"))
    )
    (net (code "39") (name "unconnected-(J10-RX2+-PadA11)") (class "Default")
      (node (ref "J10") (pin "A11") (pinfunction "RX2+_A11") (pintype "bidirectional+no_connect"))
    )
    (net (code "40") (name "unconnected-(J10-RX2--PadA10)") (class "Default")
      (node (ref "J10") (pin "A10") (pinfunction "RX2-_A10") (pintype "bidirectional+no_connect"))
    )
    (net (code "41") (name "unconnected-(J10-SBU1-PadA8)") (class "Default")
      (node (ref "J10") (pin "A8") (pinfunction "SBU1_A8") (pintype "bidirectional"))
    )
    (net (code "42") (name "unconnected-(J10-SBU2-PadB8)") (class "Default")
      (node (ref "J10") (pin "B8") (pinfunction "SBU2_B8") (pintype "bidirectional"))
    )
    (net (code "43") (name "unconnected-(J10-TX1+-PadA2)") (class "Default")
      (node (ref "J10") (pin "A2") (pinfunction "TX1+_A2") (pintype "bidirectional+no_connect"))
    )
    (net (code "44") (name "unconnected-(J10-TX1--PadA3)") (class "Default")
      (node (ref "J10") (pin "A3") (pinfunction "TX1-_A3") (pintype "bidirectional+no_connect"))
    )
    (net (code "45") (name "unconnected-(J10-TX2+-PadB2)") (class "Default")
      (node (ref "J10") (pin "B2") (pinfunction "TX2+_B2") (pintype "bidirectional+no_connect"))
    )
    (net (code "46") (name "unconnected-(J10-TX2--PadB3)") (class "Default")
      (node (ref "J10") (pin "B3") (pinfunction "TX2-_B3") (pintype "bidirectional+no_connect"))
    )
    (net (code "47") (name "unconnected-(U25-GPIO0-Pad5)") (class "Default")
      (node (ref "U25") (pin "5") (pinfunction "GPIO0_5") (pintype "bidirectional"))
    )
    (net (code "48") (name "unconnected-(U25-GPIO1-Pad6)") (class "Default")
      (node (ref "U25") (pin "6") (pinfunction "GPIO1_6") (pintype "bidirectional"))
    )
    (net (code "49") (name "unconnected-(U25-GPIO2-Pad7)") (class "Default")
      (node (ref "U25") (pin "7") (pinfunction "GPIO2_7") (pintype "bidirectional"))
    )
    (net (code "50") (name "unconnected-(U25-GPIO3-Pad19)") (class "Default")
      (node (ref "U25") (pin "19") (pinfunction "GPIO3_19") (pintype "bidirectional"))
    )
    (net (code "51") (name "unconnected-(U25-GPIO6-Pad37)") (class "Default")
      (node (ref "U25") (pin "37") (pinfunction "GPIO6_37") (pintype "bidirectional"))
    )
    (net (code "52") (name "unconnected-(U25-GPIO7-Pad36)") (class "Default")
      (node (ref "U25") (pin "36") (pinfunction "GPIO7_36") (pintype "bidirectional"))
    )
    (net (code "53") (name "unconnected-(U25-GPIO11-Pad13)") (class "Default")
      (node (ref "U25") (pin "13") (pinfunction "GPIO11_13") (pintype "bidirectional"))
    )
    (net (code "54") (name "unconnected-(U27-D+-Pad6)") (class "Default")
      (node (ref "U27") (pin "6") (pinfunction "D+_6") (pintype "passive+no_connect"))
    )
    (net (code "55") (name "unconnected-(U27-D--Pad7)") (class "Default")
      (node (ref "U27") (pin "7") (pinfunction "D-_7") (pintype "passive+no_connect"))
    )
    (net (code "56") (name "unconnected-(U27-~{INT}-Pad21)") (class "Default")
      (node (ref "U27") (pin "21") (pinfunction "~{INT}_21") (pintype "passive"))
    )
    (net (code "57") (name "unconnected-(U27-~{QON}-Pad12)") (class "Default")
      (node (ref "U27") (pin "12") (pinfunction "~{QON}_12") (pintype "passive+no_connect"))
    )
  )
)
